# SWITCHING.net
KiCad netlist of a schematic drawn in Altium Designer
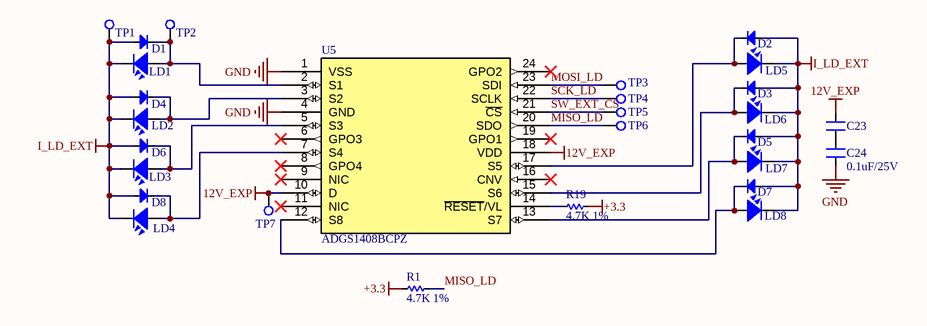
[diagram p0: SWITCHING.SchDoc]

(export (version "E")
  (design (tool "Eeschema 10.0.6"))
  (components
    (comp (ref "C23")
      (value "0.1uF/25V")
      (footprint "SM-0603")
      (description "0603")
      (libsource (lib "Capacitors") (part "CM"))
    )
    (comp (ref "C24")
      (value "0.1uF/25V")
      (footprint "SM-0603")
      (description "0603")
      (libsource (lib "Capacitors") (part "CM"))
    )
    (comp (ref "D1")
      (value "1N4148W-TP")
      (footprint "SOD23")
      (description "DIODE GEN PURP 100V 150MA SOD123")
      (fields (field (name "PUBLISHER") "Altium Limited"))
      (libsource (lib "Library") (part "Diode SMD"))
    )
    (comp (ref "D2")
      (value "1N4148W-TP")
      (footprint "SOD23")
      (description "DIODE GEN PURP 100V 150MA SOD123")
      (fields (field (name "PUBLISHER") "Altium Limited"))
      (libsource (lib "Library") (part "Diode SMD"))
    )
    (comp (ref "D3")
      (value "1N4148W-TP")
      (footprint "SOD23")
      (description "DIODE GEN PURP 100V 150MA SOD123")
      (fields (field (name "PUBLISHER") "Altium Limited"))
      (libsource (lib "Library") (part "Diode SMD"))
    )
    (comp (ref "D4")
      (value "1N4148W-TP")
      (footprint "SOD23")
      (description "DIODE GEN PURP 100V 150MA SOD123")
      (fields (field (name "PUBLISHER") "Altium Limited"))
      (libsource (lib "Library") (part "Diode SMD"))
    )
    (comp (ref "D5")
      (value "1N4148W-TP")
      (footprint "SOD23")
      (description "DIODE GEN PURP 100V 150MA SOD123")
      (fields (field (name "PUBLISHER") "Altium Limited"))
      (libsource (lib "Library") (part "Diode SMD"))
    )
    (comp (ref "D6")
      (value "1N4148W-TP")
      (footprint "SOD23")
      (description "DIODE GEN PURP 100V 150MA SOD123")
      (fields (field (name "PUBLISHER") "Altium Limited"))
      (libsource (lib "Library") (part "Diode SMD"))
    )
    (comp (ref "D7")
      (value "1N4148W-TP")
      (footprint "SOD23")
      (description "DIODE GEN PURP 100V 150MA SOD123")
      (fields (field (name "PUBLISHER") "Altium Limited"))
      (libsource (lib "Library") (part "Diode SMD"))
    )
    (comp (ref "D8")
      (value "1N4148W-TP")
      (footprint "SOD23")
      (description "DIODE GEN PURP 100V 150MA SOD123")
      (fields (field (name "PUBLISHER") "Altium Limited"))
      (libsource (lib "Library") (part "Diode SMD"))
    )
    (comp (ref "LD1") (value "LaserDiode") (footprint "LASER") (libsource (lib "Library") (part "LD")))
    (comp (ref "LD2") (value "LaserDiode") (footprint "LASER") (libsource (lib "Library") (part "LD")))
    (comp (ref "LD3") (value "LaserDiode") (footprint "LASER") (libsource (lib "Library") (part "LD")))
    (comp (ref "LD4") (value "LaserDiode") (footprint "LASER") (libsource (lib "Library") (part "LD")))
    (comp (ref "LD5") (value "LaserDiode") (footprint "LASER") (libsource (lib "Library") (part "LD")))
    (comp (ref "LD6") (value "LaserDiode") (footprint "LASER") (libsource (lib "Library") (part "LD")))
    (comp (ref "LD7") (value "LaserDiode") (footprint "LASER") (libsource (lib "Library") (part "LD")))
    (comp (ref "LD8") (value "LaserDiode") (footprint "LASER") (libsource (lib "Library") (part "LD")))
    (comp (ref "R1")
      (value "4.7K 1%")
      (footprint "RES-SMD-0603")
      (description "0603")
      (fields
        (field (name "MANUFACTURER") "Generic Components")
        (field (name "PUBLISHER") "Altium Hobart Technology Centre")
      )
      (libsource (lib "Library") (part "Res-SMD"))
    )
    (comp (ref "R19")
      (value "4.7K 1%")
      (footprint "RES-SMD-0603")
      (description "0603")
      (fields
        (field (name "MANUFACTURER") "Generic Components")
        (field (name "PUBLISHER") "Altium Hobart Technology Centre")
      )
      (libsource (lib "Library") (part "Res-SMD"))
    )
    (comp (ref "TP1")
      (value "Test_Point")
      (footprint "TESTPOINT")
      (libsource (lib "Library_HUNG") (part "Test_Point"))
    )
    (comp (ref "TP2")
      (value "Test_Point")
      (footprint "TESTPOINT")
      (libsource (lib "Library_HUNG") (part "Test_Point"))
    )
    (comp (ref "TP3")
      (value "Test_Point")
      (footprint "TESTPOINT")
      (libsource (lib "Library_HUNG") (part "Test_Point"))
    )
    (comp (ref "TP4")
      (value "Test_Point")
      (footprint "TESTPOINT")
      (libsource (lib "Library_HUNG") (part "Test_Point"))
    )
    (comp (ref "TP5")
      (value "Test_Point")
      (footprint "TESTPOINT")
      (libsource (lib "Library_HUNG") (part "Test_Point"))
    )
    (comp (ref "TP6")
      (value "Test_Point")
      (footprint "TESTPOINT")
      (libsource (lib "Library_HUNG") (part "Test_Point"))
    )
    (comp (ref "TP7")
      (value "Test_Point")
      (footprint "TESTPOINT")
      (libsource (lib "Library_HUNG") (part "Test_Point"))
    )
    (comp (ref "U5")
      (value "ADGS1408BCPZ")
      (footprint "ADGS1408BCPZ")
      (description "IC MUX 8:1 4.7OHM 24LFCSP")
      (libsource (lib "Library") (part "ADGS1408"))
    )
  )
  (nets
    (net (code "1") (name "+3.3") (class "Default")
      (node (ref "R1") (pin "2") (pinfunction "2_2") (pintype "passive"))
      (node (ref "R19") (pin "2") (pinfunction "2_2") (pintype "passive"))
    )
    (net (code "2") (name "/MISO_LD") (class "Default")
      (node (ref "R1") (pin "1") (pinfunction "1_1") (pintype "passive"))
      (node (ref "TP6") (pin "1") (pintype "power_in"))
      (node (ref "U5") (pin "20") (pinfunction "SDO_20") (pintype "output"))
    )
    (net (code "3") (name "/MOSI_LD") (class "Default")
      (node (ref "TP3") (pin "1") (pintype "power_in"))
      (node (ref "U5") (pin "23") (pinfunction "SDI_23") (pintype "input"))
    )
    (net (code "4") (name "/SCK_LD") (class "Default")
      (node (ref "TP4") (pin "1") (pintype "power_in"))
      (node (ref "U5") (pin "22") (pinfunction "SCLK_22") (pintype "input"))
    )
    (net (code "5") (name "/SW_EXT_CS") (class "Default")
      (node (ref "TP5") (pin "1") (pintype "power_in"))
      (node (ref "U5") (pin "21") (pinfunction "~{CS}_21") (pintype "input"))
    )
    (net (code "6") (name "12V_EXP") (class "Default")
      (node (ref "C23") (pin "2") (pinfunction "2_2") (pintype "passive"))
      (node (ref "TP7") (pin "1") (pintype "power_in"))
      (node (ref "U5") (pin "10") (pinfunction "D_10") (pintype "bidirectional"))
      (node (ref "U5") (pin "18") (pinfunction "VDD_18") (pintype "power_in"))
    )
    (net (code "7") (name "GND") (class "Default")
      (node (ref "C24") (pin "1") (pinfunction "1_1") (pintype "passive"))
      (node (ref "U5") (pin "1") (pinfunction "VSS_1") (pintype "power_in"))
      (node (ref "U5") (pin "4") (pinfunction "GND_4") (pintype "power_in"))
    )
    (net (code "8") (name "I_LD_EXT") (class "Default")
      (node (ref "D1") (pin "1") (pinfunction "A_1") (pintype "passive"))
      (node (ref "D2") (pin "1") (pinfunction "A_1") (pintype "passive"))
      (node (ref "D3") (pin "1") (pinfunction "A_1") (pintype "passive"))
      (node (ref "D4") (pin "1") (pinfunction "A_1") (pintype "passive"))
      (node (ref "D5") (pin "1") (pinfunction "A_1") (pintype "passive"))
      (node (ref "D6") (pin "1") (pinfunction "A_1") (pintype "passive"))
      (node (ref "D7") (pin "1") (pinfunction "A_1") (pintype "passive"))
      (node (ref "D8") (pin "1") (pinfunction "A_1") (pintype "passive"))
      (node (ref "LD1") (pin "3") (pinfunction "3_3") (pintype "passive"))
      (node (ref "LD2") (pin "3") (pinfunction "3_3") (pintype "passive"))
      (node (ref "LD3") (pin "3") (pinfunction "3_3") (pintype "passive"))
      (node (ref "LD4") (pin "3") (pinfunction "3_3") (pintype "passive"))
      (node (ref "LD5") (pin "3") (pinfunction "3_3") (pintype "passive"))
      (node (ref "LD6") (pin "3") (pinfunction "3_3") (pintype "passive"))
      (node (ref "LD7") (pin "3") (pinfunction "3_3") (pintype "passive"))
      (node (ref "LD8") (pin "3") (pinfunction "3_3") (pintype "passive"))
      (node (ref "TP1") (pin "1") (pintype "power_in"))
    )
    (net (code "9") (name "Net-(C23-Pad1)") (class "Default")
      (node (ref "C23") (pin "1") (pinfunction "1_1") (pintype "passive"))
      (node (ref "C24") (pin "2") (pinfunction "2_2") (pintype "passive"))
    )
    (net (code "10") (name "Net-(D1-K)") (class "Default")
      (node (ref "D1") (pin "2") (pinfunction "K_2") (pintype "passive"))
      (node (ref "LD1") (pin "1") (pinfunction "1_1") (pintype "passive"))
      (node (ref "TP2") (pin "1") (pintype "power_in"))
      (node (ref "U5") (pin "2") (pinfunction "S1_2") (pintype "bidirectional"))
    )
    (net (code "11") (name "Net-(D2-K)") (class "Default")
      (node (ref "D2") (pin "2") (pinfunction "K_2") (pintype "passive"))
      (node (ref "LD5") (pin "1") (pinfunction "1_1") (pintype "passive"))
      (node (ref "U5") (pin "17") (pinfunction "S5_17") (pintype "bidirectional"))
    )
    (net (code "12") (name "Net-(D3-K)") (class "Default")
      (node (ref "D3") (pin "2") (pinfunction "K_2") (pintype "passive"))
      (node (ref "LD6") (pin "1") (pinfunction "1_1") (pintype "passive"))
      (node (ref "U5") (pin "15") (pinfunction "S6_15") (pintype "bidirectional"))
    )
    (net (code "13") (name "Net-(D4-K)") (class "Default")
      (node (ref "D4") (pin "2") (pinfunction "K_2") (pintype "passive"))
      (node (ref "LD2") (pin "1") (pinfunction "1_1") (pintype "passive"))
      (node (ref "U5") (pin "3") (pinfunction "S2_3") (pintype "bidirectional"))
    )
    (net (code "14") (name "Net-(D5-K)") (class "Default")
      (node (ref "D5") (pin "2") (pinfunction "K_2") (pintype "passive"))
      (node (ref "LD7") (pin "1") (pinfunction "1_1") (pintype "passive"))
      (node (ref "U5") (pin "13") (pinfunction "S7_13") (pintype "bidirectional"))
    )
    (net (code "15") (name "Net-(D6-K)") (class "Default")
      (node (ref "D6") (pin "2") (pinfunction "K_2") (pintype "passive"))
      (node (ref "LD3") (pin "1") (pinfunction "1_1") (pintype "passive"))
      (node (ref "U5") (pin "5") (pinfunction "S3_5") (pintype "bidirectional"))
    )
    (net (code "16") (name "Net-(D7-K)") (class "Default")
      (node (ref "D7") (pin "2") (pinfunction "K_2") (pintype "passive"))
      (node (ref "LD8") (pin "1") (pinfunction "1_1") (pintype "passive"))
      (node (ref "U5") (pin "12") (pinfunction "S8_12") (pintype "bidirectional"))
    )
    (net (code "17") (name "Net-(D8-K)") (class "Default")
      (node (ref "D8") (pin "2") (pinfunction "K_2") (pintype "passive"))
      (node (ref "LD4") (pin "1") (pinfunction "1_1") (pintype "passive"))
      (node (ref "U5") (pin "7") (pinfunction "S4_7") (pintype "bidirectional"))
    )
    (net (code "18") (name "Net-(U5-~{RESET}{slash}VL)") (class "Default")
      (node (ref "R19") (pin "1") (pinfunction "1_1") (pintype "passive"))
      (node (ref "U5") (pin "14") (pinfunction "~{RESET}/VL_14") (pintype "passive"))
    )
    (net (code "19") (name "unconnected-(U5-CNV-Pad16)") (class "Default")
      (node (ref "U5") (pin "16") (pinfunction "CNV_16") (pintype "input+no_connect"))
    )
    (net (code "20") (name "unconnected-(U5-GPO1-Pad19)") (class "Default")
      (node (ref "U5") (pin "19") (pinfunction "GPO1_19") (pintype "output+no_connect"))
    )
    (net (code "21") (name "unconnected-(U5-GPO2-Pad24)") (class "Default")
      (node (ref "U5") (pin "24") (pinfunction "GPO2_24") (pintype "output+no_connect"))
    )
    (net (code "22") (name "unconnected-(U5-GPO3-Pad6)") (class "Default")
      (node (ref "U5") (pin "6") (pinfunction "GPO3_6") (pintype "output+no_connect"))
    )
    (net (code "23") (name "unconnected-(U5-GPO4-Pad8)") (class "Default")
      (node (ref "U5") (pin "8") (pinfunction "GPO4_8") (pintype "output+no_connect"))
    )
    (net (code "24") (name "unconnected-(U5-NIC-Pad9)") (class "Default")
      (node (ref "U5") (pin "9") (pinfunction "NIC_9") (pintype "passive+no_connect"))
    )
    (net (code "25") (name "unconnected-(U5-NIC-Pad11)") (class "Default")
      (node (ref "U5") (pin "11") (pinfunction "NIC_11") (pintype "passive+no_connect"))
    )
  )
)
